# design.net
KiCad netlist of a schematic drawn in Altium Designer
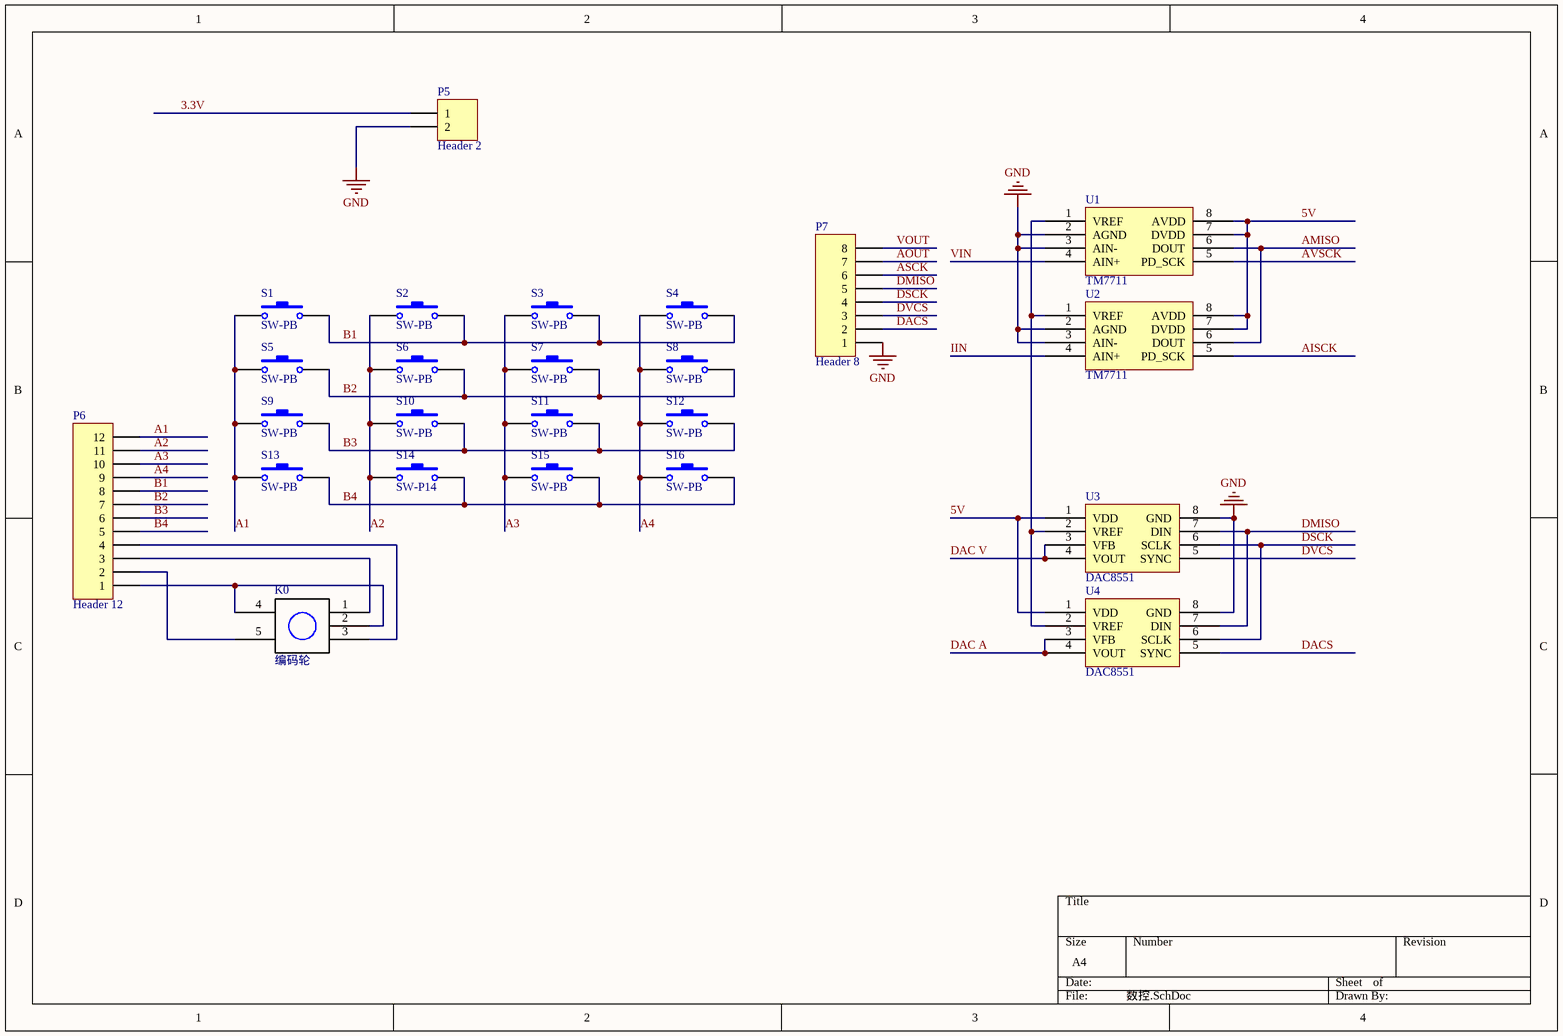
[diagram p0: 数控.SchDoc]

(export (version "E")
  (design (tool "Eeschema 10.0.6"))
  (components
    (comp (ref "K0") (value "编码轮") (libsource (lib "Lib") (part "编码轮")))
    (comp (ref "P5")
      (value "Header 2")
      (footprint "HDR1X2")
      (description "Header, 2-Pin")
      (fields (field (name "PUBLISHER") "Altium Limited"))
      (libsource (lib "Miscellaneous Connectors") (part "Header 2"))
    )
    (comp (ref "P6")
      (value "Header 12")
      (footprint "HDR1X12")
      (description "Header, 12-Pin")
      (fields (field (name "PUBLISHER") "Altium Limited"))
      (libsource (lib "Miscellaneous Connectors") (part "Header 12"))
    )
    (comp (ref "P7")
      (value "Header 8")
      (footprint "HDR1X8")
      (description "Header, 8-Pin")
      (fields (field (name "PUBLISHER") "Altium Limited"))
      (libsource (lib "Miscellaneous Connectors") (part "Header 8"))
    )
    (comp (ref "S1")
      (value "SW-PB")
      (footprint "SPST-2")
      (description "Switch")
      (fields (field (name "PUBLISHER") "Altium Limited"))
      (libsource (lib "Miscellaneous Devices") (part "SW-PB"))
    )
    (comp (ref "S2")
      (value "SW-PB")
      (footprint "SPST-2")
      (description "Switch")
      (fields (field (name "PUBLISHER") "Altium Limited"))
      (libsource (lib "Miscellaneous Devices") (part "SW-PB"))
    )
    (comp (ref "S3")
      (value "SW-PB")
      (footprint "SPST-2")
      (description "Switch")
      (fields (field (name "PUBLISHER") "Altium Limited"))
      (libsource (lib "Miscellaneous Devices") (part "SW-PB"))
    )
    (comp (ref "S4")
      (value "SW-PB")
      (footprint "SPST-2")
      (description "Switch")
      (fields (field (name "PUBLISHER") "Altium Limited"))
      (libsource (lib "Miscellaneous Devices") (part "SW-PB"))
    )
    (comp (ref "S5")
      (value "SW-PB")
      (footprint "SPST-2")
      (description "Switch")
      (fields (field (name "PUBLISHER") "Altium Limited"))
      (libsource (lib "Miscellaneous Devices") (part "SW-PB"))
    )
    (comp (ref "S6")
      (value "SW-PB")
      (footprint "SPST-2")
      (description "Switch")
      (fields (field (name "PUBLISHER") "Altium Limited"))
      (libsource (lib "Miscellaneous Devices") (part "SW-PB"))
    )
    (comp (ref "S7")
      (value "SW-PB")
      (footprint "SPST-2")
      (description "Switch")
      (fields (field (name "PUBLISHER") "Altium Limited"))
      (libsource (lib "Miscellaneous Devices") (part "SW-PB"))
    )
    (comp (ref "S8")
      (value "SW-PB")
      (footprint "SPST-2")
      (description "Switch")
      (fields (field (name "PUBLISHER") "Altium Limited"))
      (libsource (lib "Miscellaneous Devices") (part "SW-PB"))
    )
    (comp (ref "S9")
      (value "SW-PB")
      (footprint "SPST-2")
      (description "Switch")
      (fields (field (name "PUBLISHER") "Altium Limited"))
      (libsource (lib "Miscellaneous Devices") (part "SW-PB"))
    )
    (comp (ref "S10")
      (value "SW-PB")
      (footprint "SPST-2")
      (description "Switch")
      (fields (field (name "PUBLISHER") "Altium Limited"))
      (libsource (lib "Miscellaneous Devices") (part "SW-PB"))
    )
    (comp (ref "S11")
      (value "SW-PB")
      (footprint "SPST-2")
      (description "Switch")
      (fields (field (name "PUBLISHER") "Altium Limited"))
      (libsource (lib "Miscellaneous Devices") (part "SW-PB"))
    )
    (comp (ref "S12")
      (value "SW-PB")
      (footprint "SPST-2")
      (description "Switch")
      (fields (field (name "PUBLISHER") "Altium Limited"))
      (libsource (lib "Miscellaneous Devices") (part "SW-PB"))
    )
    (comp (ref "S13")
      (value "SW-PB")
      (footprint "SPST-2")
      (description "Switch")
      (fields (field (name "PUBLISHER") "Altium Limited"))
      (libsource (lib "Miscellaneous Devices") (part "SW-PB"))
    )
    (comp (ref "S14")
      (value "SW-P14")
      (footprint "SPST-2")
      (description "Switch")
      (fields (field (name "PUBLISHER") "Altium Limited"))
      (libsource (lib "Miscellaneous Devices") (part "SW-PB"))
    )
    (comp (ref "S15")
      (value "SW-PB")
      (footprint "SPST-2")
      (description "Switch")
      (fields (field (name "PUBLISHER") "Altium Limited"))
      (libsource (lib "Miscellaneous Devices") (part "SW-PB"))
    )
    (comp (ref "S16")
      (value "SW-PB")
      (footprint "SPST-2")
      (description "Switch")
      (fields (field (name "PUBLISHER") "Altium Limited"))
      (libsource (lib "Miscellaneous Devices") (part "SW-PB"))
    )
    (comp (ref "U1") (value "TM7711") (libsource (lib "Lib") (part "TM7711")))
    (comp (ref "U2") (value "TM7711") (libsource (lib "Lib") (part "TM7711")))
    (comp (ref "U3") (value "DAC8551") (libsource (lib "Lib") (part "DAC8551")))
    (comp (ref "U4") (value "DAC8551") (libsource (lib "Lib") (part "DAC8551")))
  )
  (nets
    (net (code "1") (name "/3.3V") (class "Default")
      (node (ref "P5") (pin "1") (pinfunction "1_1") (pintype "passive"))
    )
    (net (code "2") (name "/5V") (class "Default")
      (node (ref "U1") (pin "7") (pinfunction "DVDD_7") (pintype "passive"))
      (node (ref "U1") (pin "8") (pinfunction "AVDD_8") (pintype "passive"))
      (node (ref "U2") (pin "7") (pinfunction "DVDD_7") (pintype "passive"))
      (node (ref "U2") (pin "8") (pinfunction "AVDD_8") (pintype "passive"))
      (node (ref "U3") (pin "1") (pinfunction "VDD_1") (pintype "passive"))
      (node (ref "U4") (pin "1") (pinfunction "VDD_1") (pintype "passive"))
    )
    (net (code "3") (name "/A1") (class "Default")
      (node (ref "P6") (pin "12") (pinfunction "12_12") (pintype "passive"))
      (node (ref "S1") (pin "1") (pinfunction "1_1") (pintype "passive"))
      (node (ref "S13") (pin "1") (pinfunction "1_1") (pintype "passive"))
      (node (ref "S5") (pin "1") (pinfunction "1_1") (pintype "passive"))
      (node (ref "S9") (pin "1") (pinfunction "1_1") (pintype "passive"))
    )
    (net (code "4") (name "/A2") (class "Default")
      (node (ref "P6") (pin "11") (pinfunction "11_11") (pintype "passive"))
      (node (ref "S10") (pin "1") (pinfunction "1_1") (pintype "passive"))
      (node (ref "S14") (pin "1") (pinfunction "1_1") (pintype "passive"))
      (node (ref "S2") (pin "1") (pinfunction "1_1") (pintype "passive"))
      (node (ref "S6") (pin "1") (pinfunction "1_1") (pintype "passive"))
    )
    (net (code "5") (name "/A3") (class "Default")
      (node (ref "P6") (pin "10") (pinfunction "10_10") (pintype "passive"))
      (node (ref "S11") (pin "1") (pinfunction "1_1") (pintype "passive"))
      (node (ref "S15") (pin "1") (pinfunction "1_1") (pintype "passive"))
      (node (ref "S3") (pin "1") (pinfunction "1_1") (pintype "passive"))
      (node (ref "S7") (pin "1") (pinfunction "1_1") (pintype "passive"))
    )
    (net (code "6") (name "/A4") (class "Default")
      (node (ref "P6") (pin "9") (pinfunction "9_9") (pintype "passive"))
      (node (ref "S12") (pin "1") (pinfunction "1_1") (pintype "passive"))
      (node (ref "S16") (pin "1") (pinfunction "1_1") (pintype "passive"))
      (node (ref "S4") (pin "1") (pinfunction "1_1") (pintype "passive"))
      (node (ref "S8") (pin "1") (pinfunction "1_1") (pintype "passive"))
    )
    (net (code "7") (name "/AISCK") (class "Default")
      (node (ref "U2") (pin "5") (pinfunction "PD_SCK_5") (pintype "passive"))
    )
    (net (code "8") (name "/AMISO") (class "Default")
      (node (ref "U1") (pin "6") (pinfunction "DOUT_6") (pintype "passive"))
      (node (ref "U2") (pin "6") (pinfunction "DOUT_6") (pintype "passive"))
    )
    (net (code "9") (name "/AOUT") (class "Default")
      (node (ref "P7") (pin "7") (pinfunction "7_7") (pintype "passive"))
    )
    (net (code "10") (name "/ASCK") (class "Default")
      (node (ref "P7") (pin "6") (pinfunction "6_6") (pintype "passive"))
    )
    (net (code "11") (name "/AVSCK") (class "Default")
      (node (ref "U1") (pin "5") (pinfunction "PD_SCK_5") (pintype "passive"))
    )
    (net (code "12") (name "/B1") (class "Default")
      (node (ref "P6") (pin "8") (pinfunction "8_8") (pintype "passive"))
      (node (ref "S1") (pin "2") (pinfunction "2_2") (pintype "passive"))
      (node (ref "S2") (pin "2") (pinfunction "2_2") (pintype "passive"))
      (node (ref "S3") (pin "2") (pinfunction "2_2") (pintype "passive"))
      (node (ref "S4") (pin "2") (pinfunction "2_2") (pintype "passive"))
    )
    (net (code "13") (name "/B2") (class "Default")
      (node (ref "P6") (pin "7") (pinfunction "7_7") (pintype "passive"))
      (node (ref "S5") (pin "2") (pinfunction "2_2") (pintype "passive"))
      (node (ref "S6") (pin "2") (pinfunction "2_2") (pintype "passive"))
      (node (ref "S7") (pin "2") (pinfunction "2_2") (pintype "passive"))
      (node (ref "S8") (pin "2") (pinfunction "2_2") (pintype "passive"))
    )
    (net (code "14") (name "/B3") (class "Default")
      (node (ref "P6") (pin "6") (pinfunction "6_6") (pintype "passive"))
      (node (ref "S10") (pin "2") (pinfunction "2_2") (pintype "passive"))
      (node (ref "S11") (pin "2") (pinfunction "2_2") (pintype "passive"))
      (node (ref "S12") (pin "2") (pinfunction "2_2") (pintype "passive"))
      (node (ref "S9") (pin "2") (pinfunction "2_2") (pintype "passive"))
    )
    (net (code "15") (name "/B4") (class "Default")
      (node (ref "P6") (pin "5") (pinfunction "5_5") (pintype "passive"))
      (node (ref "S13") (pin "2") (pinfunction "2_2") (pintype "passive"))
      (node (ref "S14") (pin "2") (pinfunction "2_2") (pintype "passive"))
      (node (ref "S15") (pin "2") (pinfunction "2_2") (pintype "passive"))
      (node (ref "S16") (pin "2") (pinfunction "2_2") (pintype "passive"))
    )
    (net (code "16") (name "/DAC A") (class "Default")
      (node (ref "U4") (pin "3") (pinfunction "VFB_3") (pintype "passive"))
      (node (ref "U4") (pin "4") (pinfunction "VOUT_4") (pintype "passive"))
    )
    (net (code "17") (name "/DAC V") (class "Default")
      (node (ref "U3") (pin "3") (pinfunction "VFB_3") (pintype "passive"))
      (node (ref "U3") (pin "4") (pinfunction "VOUT_4") (pintype "passive"))
    )
    (net (code "18") (name "/DACS") (class "Default")
      (node (ref "P7") (pin "2") (pinfunction "2_2") (pintype "passive"))
      (node (ref "U4") (pin "5") (pinfunction "SYNC_5") (pintype "passive"))
    )
    (net (code "19") (name "/DMISO") (class "Default")
      (node (ref "P7") (pin "5") (pinfunction "5_5") (pintype "passive"))
      (node (ref "U3") (pin "7") (pinfunction "DIN_7") (pintype "passive"))
      (node (ref "U4") (pin "7") (pinfunction "DIN_7") (pintype "passive"))
    )
    (net (code "20") (name "/DSCK") (class "Default")
      (node (ref "P7") (pin "4") (pinfunction "4_4") (pintype "passive"))
      (node (ref "U3") (pin "6") (pinfunction "SCLK_6") (pintype "passive"))
      (node (ref "U4") (pin "6") (pinfunction "SCLK_6") (pintype "passive"))
    )
    (net (code "21") (name "/DVCS") (class "Default")
      (node (ref "P7") (pin "3") (pinfunction "3_3") (pintype "passive"))
      (node (ref "U3") (pin "5") (pinfunction "SYNC_5") (pintype "passive"))
    )
    (net (code "22") (name "/IIN") (class "Default")
      (node (ref "U2") (pin "4") (pinfunction "AIN+_4") (pintype "passive"))
    )
    (net (code "23") (name "/VIN") (class "Default")
      (node (ref "U1") (pin "4") (pinfunction "AIN+_4") (pintype "passive"))
    )
    (net (code "24") (name "/VOUT") (class "Default")
      (node (ref "P7") (pin "8") (pinfunction "8_8") (pintype "passive"))
    )
    (net (code "25") (name "GND") (class "Default")
      (node (ref "P5") (pin "2") (pinfunction "2_2") (pintype "passive"))
      (node (ref "P7") (pin "1") (pinfunction "1_1") (pintype "passive"))
      (node (ref "U1") (pin "2") (pinfunction "AGND_2") (pintype "passive"))
      (node (ref "U1") (pin "3") (pinfunction "AIN-_3") (pintype "passive"))
      (node (ref "U2") (pin "2") (pinfunction "AGND_2") (pintype "passive"))
      (node (ref "U2") (pin "3") (pinfunction "AIN-_3") (pintype "passive"))
      (node (ref "U3") (pin "8") (pinfunction "GND_8") (pintype "passive"))
      (node (ref "U4") (pin "8") (pinfunction "GND_8") (pintype "passive"))
    )
    (net (code "26") (name "Net-(K0-Pad1)") (class "Default")
      (node (ref "K0") (pin "1") (pintype "passive"))
      (node (ref "P6") (pin "3") (pinfunction "3_3") (pintype "passive"))
    )
    (net (code "27") (name "Net-(K0-Pad2)") (class "Default")
      (node (ref "K0") (pin "2") (pintype "passive"))
      (node (ref "K0") (pin "4") (pintype "passive"))
      (node (ref "P6") (pin "1") (pinfunction "1_1") (pintype "passive"))
    )
    (net (code "28") (name "Net-(K0-Pad3)") (class "Default")
      (node (ref "K0") (pin "3") (pintype "passive"))
      (node (ref "P6") (pin "4") (pinfunction "4_4") (pintype "passive"))
    )
    (net (code "29") (name "Net-(K0-Pad5)") (class "Default")
      (node (ref "K0") (pin "5") (pintype "passive"))
      (node (ref "P6") (pin "2") (pinfunction "2_2") (pintype "passive"))
    )
    (net (code "30") (name "Net-(U1-VREF)") (class "Default")
      (node (ref "U1") (pin "1") (pinfunction "VREF_1") (pintype "passive"))
      (node (ref "U2") (pin "1") (pinfunction "VREF_1") (pintype "passive"))
      (node (ref "U3") (pin "2") (pinfunction "VREF_2") (pintype "passive"))
      (node (ref "U4") (pin "2") (pinfunction "VREF_2") (pintype "passive"))
    )
  )
)
